# 28Pins_Schem.net
KiCad netlist of a schematic drawn in Altium Designer
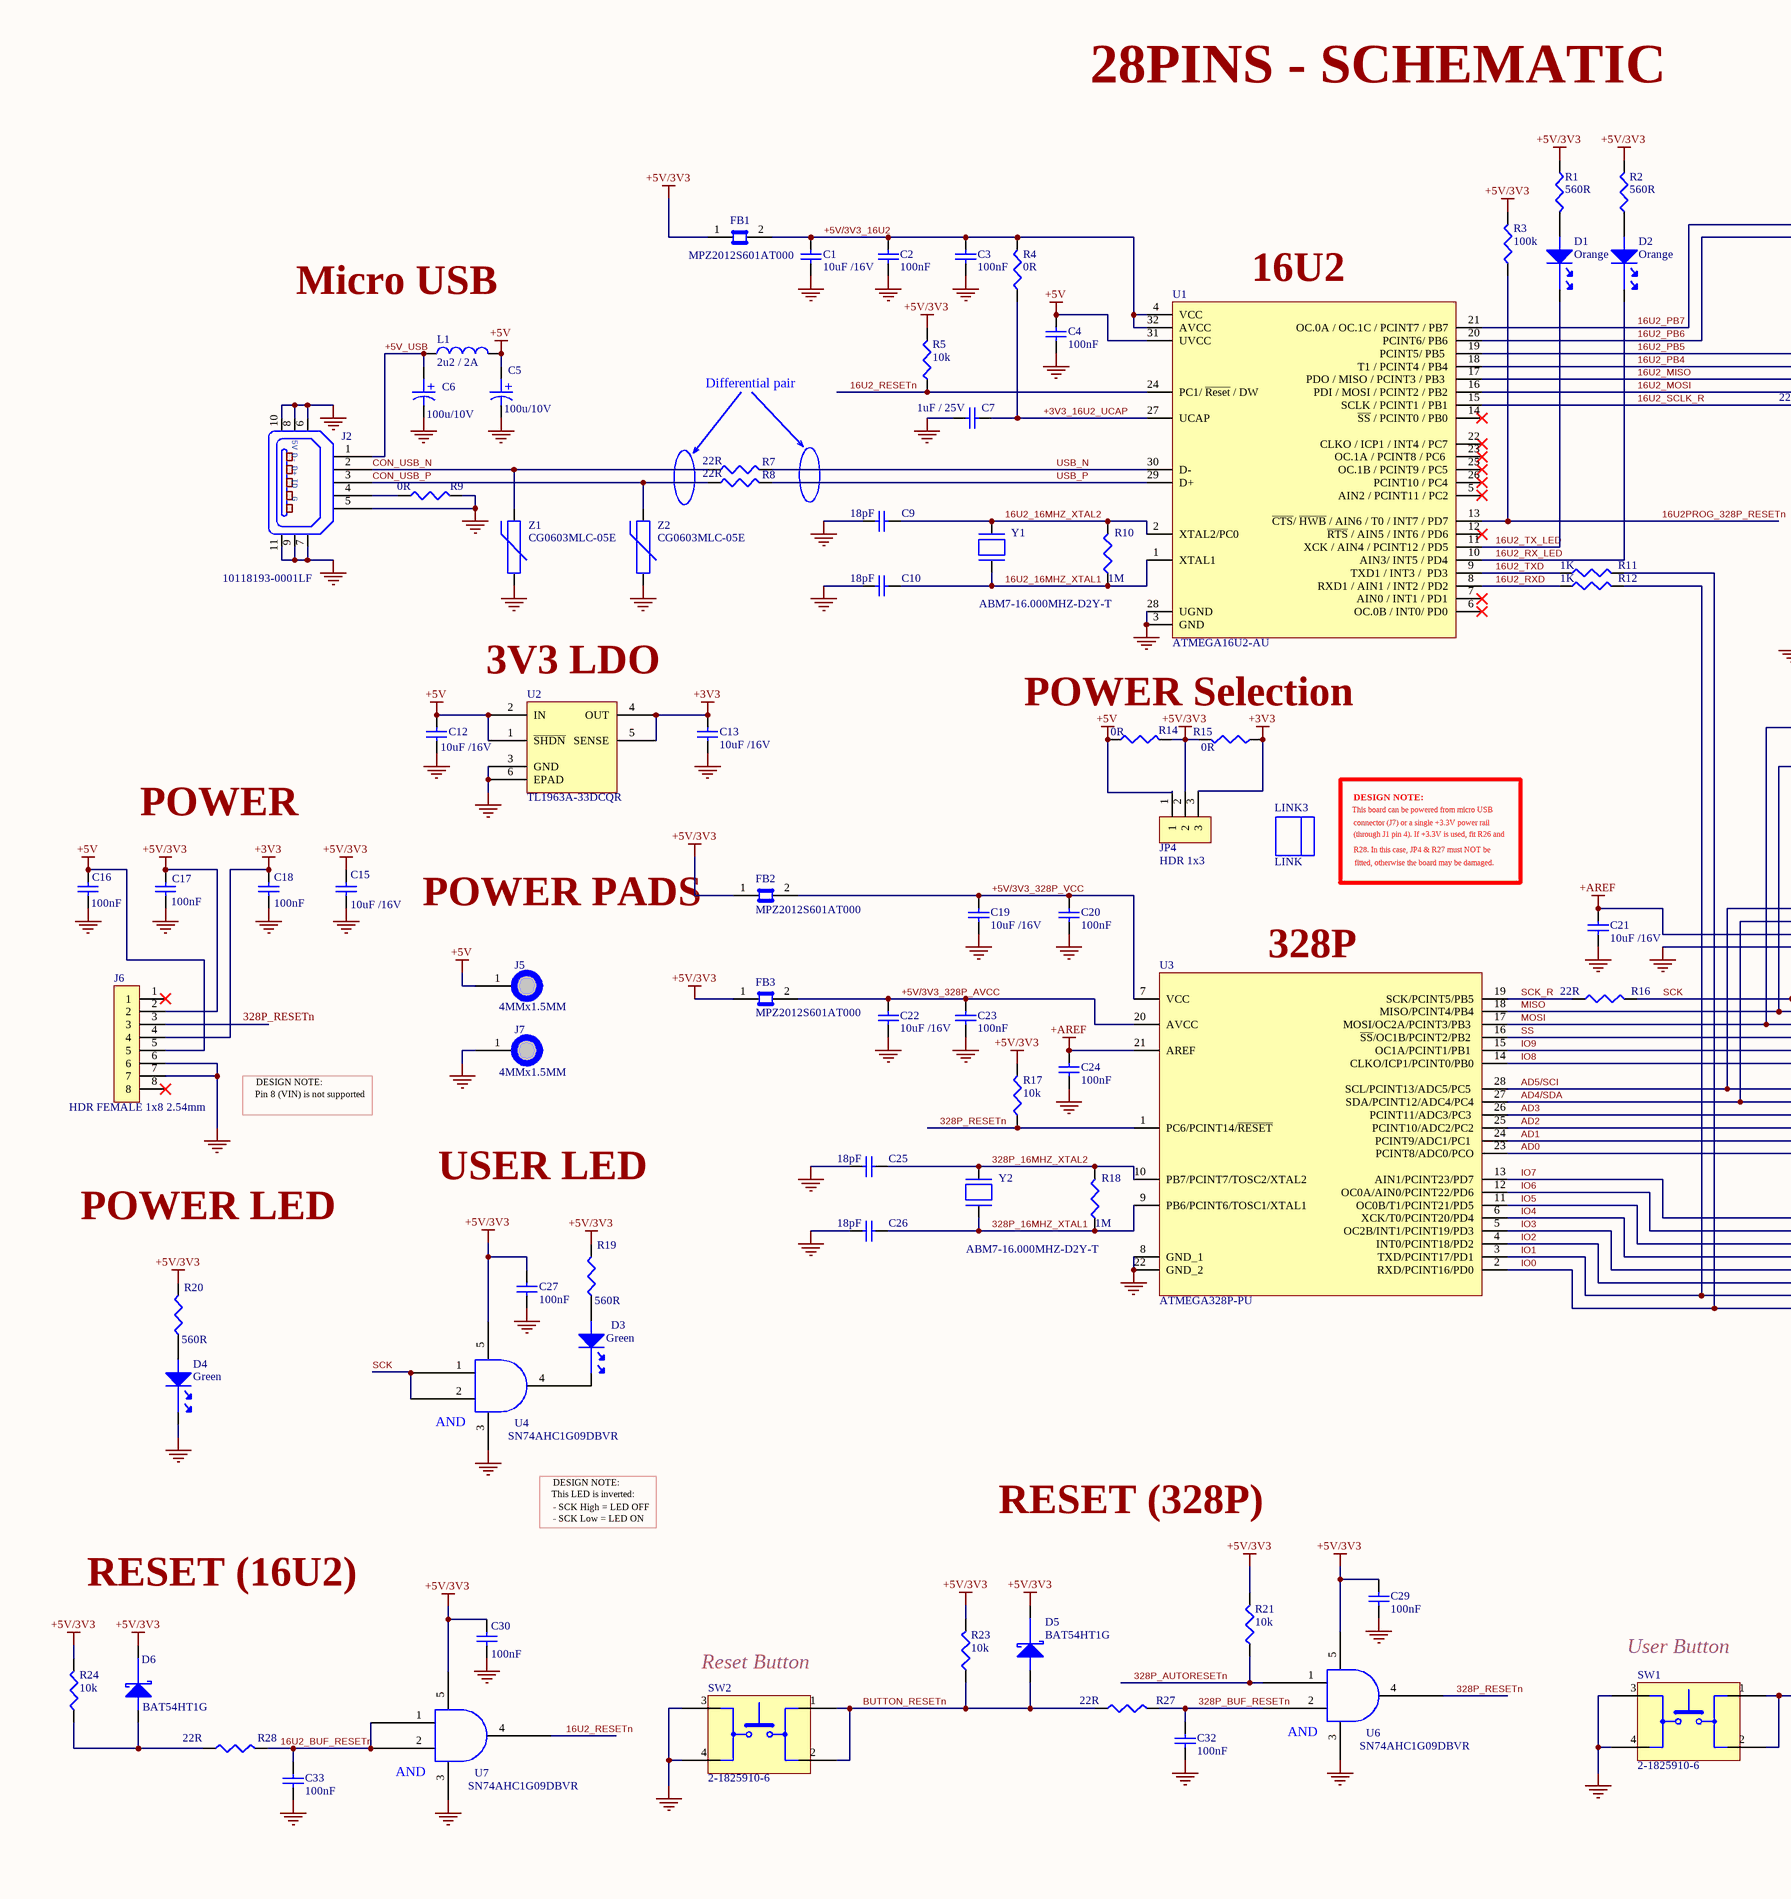
[diagram p0: 28Pins_Schem.SchDoc, left]
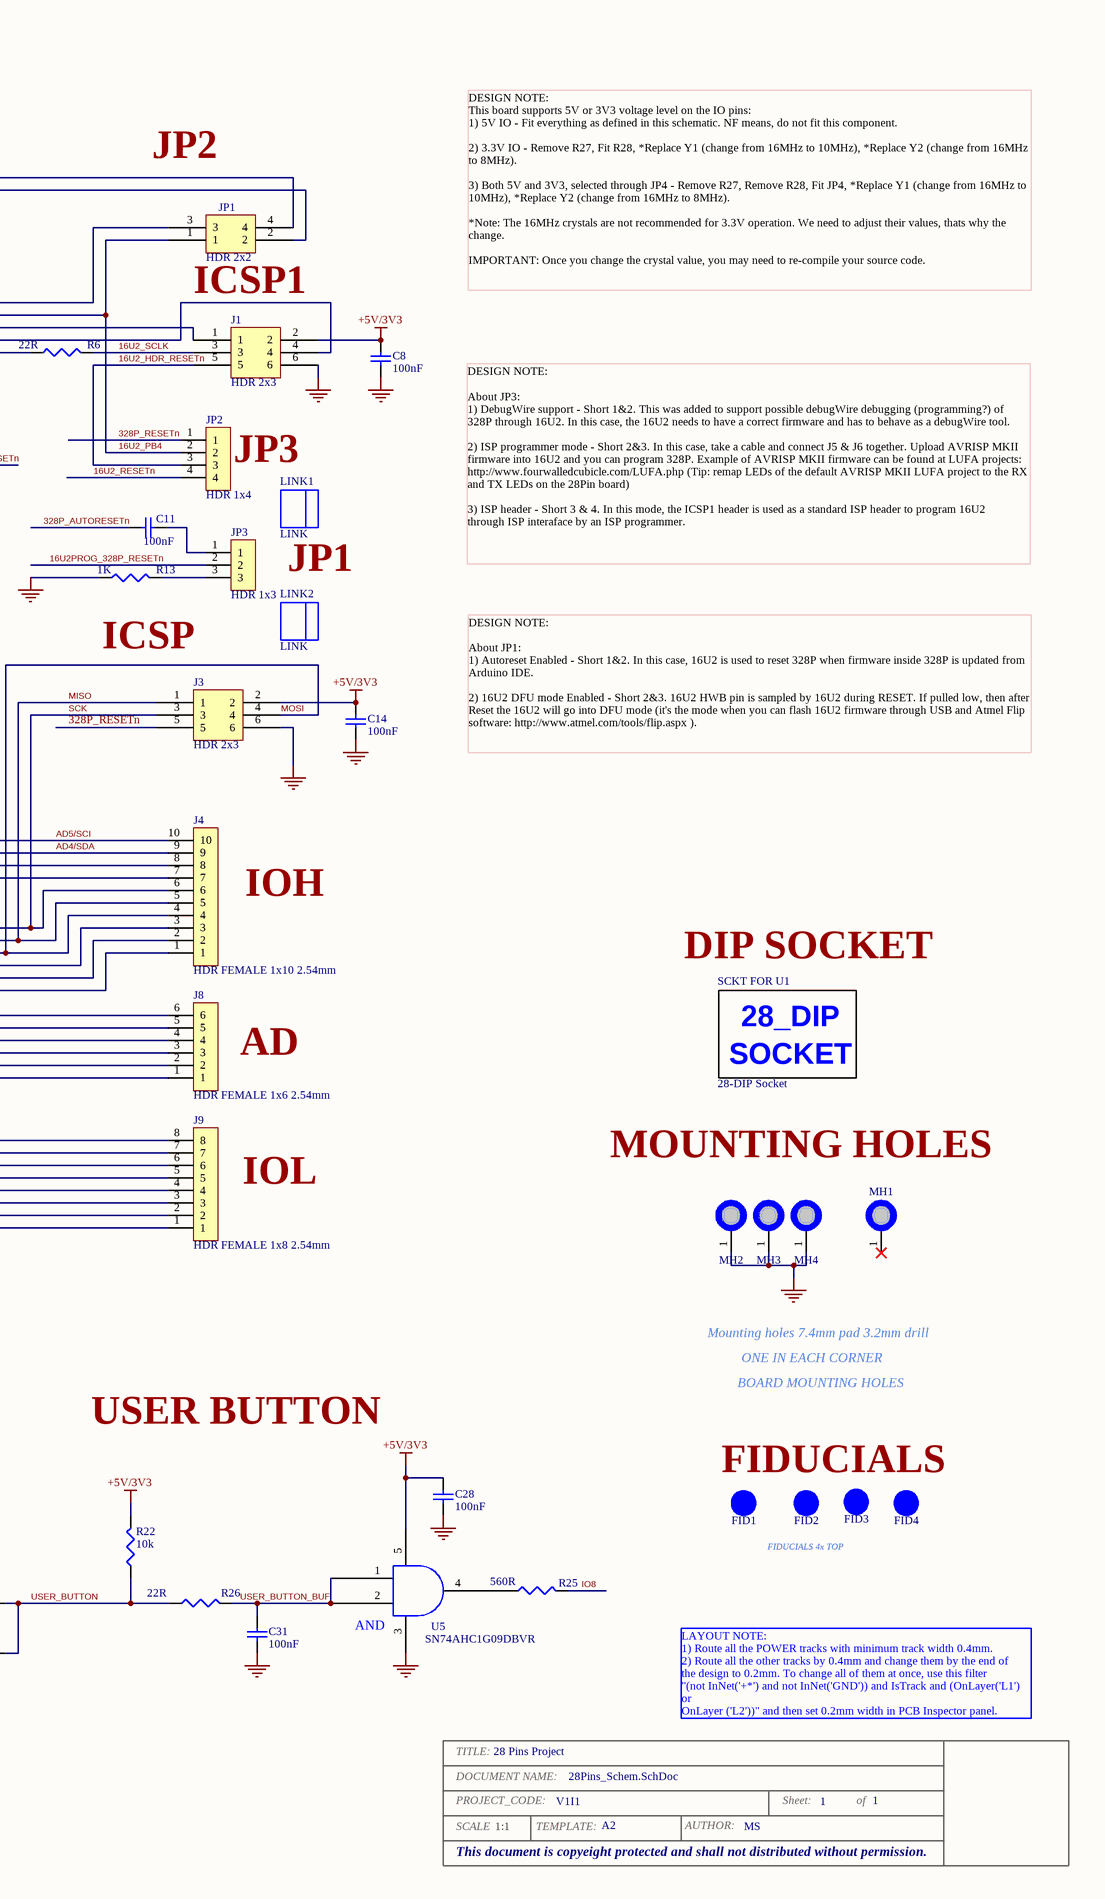
[diagram p1: 28Pins_Schem.SchDoc, right]

(export (version "E")
  (design (tool "Eeschema 10.0.6"))
  (components
    (comp (ref "28 Pins Project")
      (value "TitleBlock")
      (description "Standard Title Block")
      (fields (field (name "TEMPLATE") "A2"))
      (libsource (lib "ms_INTLIB") (part "TitleBlock"))
    )
    (comp (ref "C1")
      (value "10uF /16V")
      (footprint "C0805")
      (fields
        (field (name "MANUFACTURER") "TDK")
        (field (name "MANUFACTURER PART NUMBER") "C2012X5R1C106M125AC")
        (field (name "TOLERANCE") "20%")
      )
      (libsource (lib "28Pins_Project_Schlib") (part "C2012X5R1C106M125AC"))
    )
    (comp (ref "C2")
      (value "100nF")
      (footprint "C0805")
      (description "C Series 0805 0.1 uF 50 V ±10 % Tolerance X7R SMT Multilayer Ceramic Capacitor")
      (fields
        (field (name "MANUFACTURER") "TDK")
        (field (name "MANUFACTURER PART NUMBER") "C2012X7R1H104K085AA")
      )
      (libsource (lib "28Pins_Project_Schlib") (part "C2012X7R1H104K085AA"))
    )
    (comp (ref "C3")
      (value "100nF")
      (footprint "C0805")
      (description "C Series 0805 0.1 uF 50 V ±10 % Tolerance X7R SMT Multilayer Ceramic Capacitor")
      (fields
        (field (name "MANUFACTURER") "TDK")
        (field (name "MANUFACTURER PART NUMBER") "C2012X7R1H104K085AA")
      )
      (libsource (lib "28Pins_Project_Schlib") (part "C2012X7R1H104K085AA"))
    )
    (comp (ref "C4")
      (value "100nF")
      (footprint "C0805")
      (description "C Series 0805 0.1 uF 50 V ±10 % Tolerance X7R SMT Multilayer Ceramic Capacitor")
      (fields
        (field (name "MANUFACTURER") "TDK")
        (field (name "MANUFACTURER PART NUMBER") "C2012X7R1H104K085AA")
      )
      (libsource (lib "28Pins_Project_Schlib") (part "C2012X7R1H104K085AA"))
    )
    (comp (ref "C5")
      (value "100u/10V")
      (footprint "C_ALU_C_SIZE")
      (description "SMD Aluminum Electrolytic Capacitor 100uF ±20% 10V 1000hrs@85°C AEC_D5.0x5.4mm_SM")
      (fields
        (field (name "MANUFACTURER") "Panasonic")
        (field (name "MANUFACTURER PART NUMBER") "EEE-1AA101WR")
      )
      (libsource (lib "28Pins_Project_Schlib") (part "EEE-1AA101WR"))
    )
    (comp (ref "C6")
      (value "100u/10V")
      (footprint "C_ALU_C_SIZE")
      (description "SMD Aluminum Electrolytic Capacitor 100uF ±20% 10V 1000hrs@85°C AEC_D5.0x5.4mm_SM")
      (fields
        (field (name "MANUFACTURER") "Panasonic")
        (field (name "MANUFACTURER PART NUMBER") "EEE-1AA101WR")
      )
      (libsource (lib "28Pins_Project_Schlib") (part "EEE-1AA101WR"))
    )
    (comp (ref "C7")
      (value "1uF / 25V")
      (footprint "C0805")
      (fields
        (field (name "MANUFACTURER") "TDK")
        (field (name "MANUFACTURER PART NUMBER") "C2012X5R1E105K125AA")
        (field (name "TOLERANCE") "10%")
      )
      (libsource (lib "28Pins_Project_Schlib") (part "C2012X5R1E105K125AA"))
    )
    (comp (ref "C8")
      (value "100nF")
      (footprint "C0805")
      (description "C Series 0805 0.1 uF 50 V ±10 % Tolerance X7R SMT Multilayer Ceramic Capacitor")
      (fields
        (field (name "MANUFACTURER") "TDK")
        (field (name "MANUFACTURER PART NUMBER") "C2012X7R1H104K085AA")
      )
      (libsource (lib "28Pins_Project_Schlib") (part "C2012X7R1H104K085AA"))
    )
    (comp (ref "C9")
      (value "18pF")
      (footprint "C0805")
      (description "Cap Ceramic 18pF 50V C0G 5% SMD 0805 125C Paper T/R")
      (fields
        (field (name "MANUFACTURER") "KEMET")
        (field (name "MANUFACTURER PART NUMBER") "C0805C180J5GACTU")
      )
      (libsource (lib "28Pins_Project_Schlib") (part "C0805C180J5GACTU"))
    )
    (comp (ref "C10")
      (value "18pF")
      (footprint "C0805")
      (description "Cap Ceramic 18pF 50V C0G 5% SMD 0805 125C Paper T/R")
      (fields
        (field (name "MANUFACTURER") "KEMET")
        (field (name "MANUFACTURER PART NUMBER") "C0805C180J5GACTU")
      )
      (libsource (lib "28Pins_Project_Schlib") (part "C0805C180J5GACTU"))
    )
    (comp (ref "C11")
      (value "100nF")
      (footprint "C0805")
      (description "C Series 0805 0.1 uF 50 V ±10 % Tolerance X7R SMT Multilayer Ceramic Capacitor")
      (fields
        (field (name "MANUFACTURER") "TDK")
        (field (name "MANUFACTURER PART NUMBER") "C2012X7R1H104K085AA")
      )
      (libsource (lib "28Pins_Project_Schlib") (part "C2012X7R1H104K085AA"))
    )
    (comp (ref "C12")
      (value "10uF /16V")
      (footprint "C0805")
      (fields
        (field (name "MANUFACTURER") "TDK")
        (field (name "MANUFACTURER PART NUMBER") "C2012X5R1C106M125AC")
        (field (name "TOLERANCE") "20%")
      )
      (libsource (lib "28Pins_Project_Schlib") (part "C2012X5R1C106M125AC"))
    )
    (comp (ref "C13")
      (value "10uF /16V")
      (footprint "C0805")
      (fields
        (field (name "MANUFACTURER") "TDK")
        (field (name "MANUFACTURER PART NUMBER") "C2012X5R1C106M125AC")
        (field (name "TOLERANCE") "20%")
      )
      (libsource (lib "28Pins_Project_Schlib") (part "C2012X5R1C106M125AC"))
    )
    (comp (ref "C14")
      (value "100nF")
      (footprint "C0805")
      (description "C Series 0805 0.1 uF 50 V ±10 % Tolerance X7R SMT Multilayer Ceramic Capacitor")
      (fields
        (field (name "MANUFACTURER") "TDK")
        (field (name "MANUFACTURER PART NUMBER") "C2012X7R1H104K085AA")
      )
      (libsource (lib "28Pins_Project_Schlib") (part "C2012X7R1H104K085AA"))
    )
    (comp (ref "C15")
      (value "10uF /16V")
      (footprint "C0805")
      (fields
        (field (name "MANUFACTURER") "TDK")
        (field (name "MANUFACTURER PART NUMBER") "C2012X5R1C106M125AC")
        (field (name "TOLERANCE") "20%")
      )
      (libsource (lib "28Pins_Project_Schlib") (part "C2012X5R1C106M125AC"))
    )
    (comp (ref "C16")
      (value "100nF")
      (footprint "C0805")
      (description "C Series 0805 0.1 uF 50 V ±10 % Tolerance X7R SMT Multilayer Ceramic Capacitor")
      (fields
        (field (name "MANUFACTURER") "TDK")
        (field (name "MANUFACTURER PART NUMBER") "C2012X7R1H104K085AA")
      )
      (libsource (lib "28Pins_Project_Schlib") (part "C2012X7R1H104K085AA"))
    )
    (comp (ref "C17")
      (value "100nF")
      (footprint "C0805")
      (description "C Series 0805 0.1 uF 50 V ±10 % Tolerance X7R SMT Multilayer Ceramic Capacitor")
      (fields
        (field (name "MANUFACTURER") "TDK")
        (field (name "MANUFACTURER PART NUMBER") "C2012X7R1H104K085AA")
      )
      (libsource (lib "28Pins_Project_Schlib") (part "C2012X7R1H104K085AA"))
    )
    (comp (ref "C18")
      (value "100nF")
      (footprint "C0805")
      (description "C Series 0805 0.1 uF 50 V ±10 % Tolerance X7R SMT Multilayer Ceramic Capacitor")
      (fields
        (field (name "MANUFACTURER") "TDK")
        (field (name "MANUFACTURER PART NUMBER") "C2012X7R1H104K085AA")
      )
      (libsource (lib "28Pins_Project_Schlib") (part "C2012X7R1H104K085AA"))
    )
    (comp (ref "C19")
      (value "10uF /16V")
      (footprint "C0805")
      (fields
        (field (name "MANUFACTURER") "TDK")
        (field (name "MANUFACTURER PART NUMBER") "C2012X5R1C106M125AC")
        (field (name "TOLERANCE") "20%")
      )
      (libsource (lib "28Pins_Project_Schlib") (part "C2012X5R1C106M125AC"))
    )
    (comp (ref "C20")
      (value "100nF")
      (footprint "C0805")
      (description "C Series 0805 0.1 uF 50 V ±10 % Tolerance X7R SMT Multilayer Ceramic Capacitor")
      (fields
        (field (name "MANUFACTURER") "TDK")
        (field (name "MANUFACTURER PART NUMBER") "C2012X7R1H104K085AA")
      )
      (libsource (lib "28Pins_Project_Schlib") (part "C2012X7R1H104K085AA"))
    )
    (comp (ref "C21")
      (value "10uF /16V")
      (footprint "C0805")
      (fields
        (field (name "MANUFACTURER") "TDK")
        (field (name "MANUFACTURER PART NUMBER") "C2012X5R1C106M125AC")
        (field (name "TOLERANCE") "20%")
      )
      (libsource (lib "28Pins_Project_Schlib") (part "C2012X5R1C106M125AC"))
    )
    (comp (ref "C22")
      (value "10uF /16V")
      (footprint "C0805")
      (fields
        (field (name "MANUFACTURER") "TDK")
        (field (name "MANUFACTURER PART NUMBER") "C2012X5R1C106M125AC")
        (field (name "TOLERANCE") "20%")
      )
      (libsource (lib "28Pins_Project_Schlib") (part "C2012X5R1C106M125AC"))
    )
    (comp (ref "C23")
      (value "100nF")
      (footprint "C0805")
      (description "C Series 0805 0.1 uF 50 V ±10 % Tolerance X7R SMT Multilayer Ceramic Capacitor")
      (fields
        (field (name "MANUFACTURER") "TDK")
        (field (name "MANUFACTURER PART NUMBER") "C2012X7R1H104K085AA")
      )
      (libsource (lib "28Pins_Project_Schlib") (part "C2012X7R1H104K085AA"))
    )
    (comp (ref "C24")
      (value "100nF")
      (footprint "C0805")
      (description "C Series 0805 0.1 uF 50 V ±10 % Tolerance X7R SMT Multilayer Ceramic Capacitor")
      (fields
        (field (name "MANUFACTURER") "TDK")
        (field (name "MANUFACTURER PART NUMBER") "C2012X7R1H104K085AA")
      )
      (libsource (lib "28Pins_Project_Schlib") (part "C2012X7R1H104K085AA"))
    )
    (comp (ref "C25")
      (value "18pF")
      (footprint "C0805")
      (description "Cap Ceramic 18pF 50V C0G 5% SMD 0805 125C Paper T/R")
      (fields
        (field (name "MANUFACTURER") "KEMET")
        (field (name "MANUFACTURER PART NUMBER") "C0805C180J5GACTU")
      )
      (libsource (lib "28Pins_Project_Schlib") (part "C0805C180J5GACTU"))
    )
    (comp (ref "C26")
      (value "18pF")
      (footprint "C0805")
      (description "Cap Ceramic 18pF 50V C0G 5% SMD 0805 125C Paper T/R")
      (fields
        (field (name "MANUFACTURER") "KEMET")
        (field (name "MANUFACTURER PART NUMBER") "C0805C180J5GACTU")
      )
      (libsource (lib "28Pins_Project_Schlib") (part "C0805C180J5GACTU"))
    )
    (comp (ref "C27")
      (value "100nF")
      (footprint "C0805")
      (description "C Series 0805 0.1 uF 50 V ±10 % Tolerance X7R SMT Multilayer Ceramic Capacitor")
      (fields
        (field (name "MANUFACTURER") "TDK")
        (field (name "MANUFACTURER PART NUMBER") "C2012X7R1H104K085AA")
      )
      (libsource (lib "28Pins_Project_Schlib") (part "C2012X7R1H104K085AA"))
    )
    (comp (ref "C28")
      (value "100nF")
      (footprint "C0805")
      (description "C Series 0805 0.1 uF 50 V ±10 % Tolerance X7R SMT Multilayer Ceramic Capacitor")
      (fields
        (field (name "MANUFACTURER") "TDK")
        (field (name "MANUFACTURER PART NUMBER") "C2012X7R1H104K085AA")
      )
      (libsource (lib "28Pins_Project_Schlib") (part "C2012X7R1H104K085AA"))
    )
    (comp (ref "C29")
      (value "100nF")
      (footprint "C0805")
      (description "C Series 0805 0.1 uF 50 V ±10 % Tolerance X7R SMT Multilayer Ceramic Capacitor")
      (fields
        (field (name "MANUFACTURER") "TDK")
        (field (name "MANUFACTURER PART NUMBER") "C2012X7R1H104K085AA")
      )
      (libsource (lib "28Pins_Project_Schlib") (part "C2012X7R1H104K085AA"))
    )
    (comp (ref "C30")
      (value "100nF")
      (footprint "C0805")
      (description "C Series 0805 0.1 uF 50 V ±10 % Tolerance X7R SMT Multilayer Ceramic Capacitor")
      (fields
        (field (name "MANUFACTURER") "TDK")
        (field (name "MANUFACTURER PART NUMBER") "C2012X7R1H104K085AA")
      )
      (libsource (lib "28Pins_Project_Schlib") (part "C2012X7R1H104K085AA"))
    )
    (comp (ref "C31")
      (value "100nF")
      (footprint "C0805")
      (description "C Series 0805 0.1 uF 50 V ±10 % Tolerance X7R SMT Multilayer Ceramic Capacitor")
      (fields
        (field (name "MANUFACTURER") "TDK")
        (field (name "MANUFACTURER PART NUMBER") "C2012X7R1H104K085AA")
      )
      (libsource (lib "28Pins_Project_Schlib") (part "C2012X7R1H104K085AA"))
    )
    (comp (ref "C32")
      (value "100nF")
      (footprint "C0805")
      (description "C Series 0805 0.1 uF 50 V ±10 % Tolerance X7R SMT Multilayer Ceramic Capacitor")
      (fields
        (field (name "MANUFACTURER") "TDK")
        (field (name "MANUFACTURER PART NUMBER") "C2012X7R1H104K085AA")
      )
      (libsource (lib "28Pins_Project_Schlib") (part "C2012X7R1H104K085AA"))
    )
    (comp (ref "C33")
      (value "100nF")
      (footprint "C0805")
      (description "C Series 0805 0.1 uF 50 V ±10 % Tolerance X7R SMT Multilayer Ceramic Capacitor")
      (fields
        (field (name "MANUFACTURER") "TDK")
        (field (name "MANUFACTURER PART NUMBER") "C2012X7R1H104K085AA")
      )
      (libsource (lib "28Pins_Project_Schlib") (part "C2012X7R1H104K085AA"))
    )
    (comp (ref "D1")
      (value "Orange")
      (footprint "LED_0603")
      (description "Smartled Orange Lc")
      (fields
        (field (name "MANUFACTURER") "Osram Opto")
        (field (name "MANUFACTURER PART NUMBER") "LOL29K-H2K1-24-Z")
      )
      (libsource (lib "28Pins_Project_Schlib") (part "LOL29K-H2K1-24-Z"))
    )
    (comp (ref "D2")
      (value "Orange")
      (footprint "LED_0603")
      (description "Smartled Orange Lc")
      (fields
        (field (name "MANUFACTURER") "Osram Opto")
        (field (name "MANUFACTURER PART NUMBER") "LOL29K-H2K1-24-Z")
      )
      (libsource (lib "28Pins_Project_Schlib") (part "LOL29K-H2K1-24-Z"))
    )
    (comp (ref "D3")
      (value "Green")
      (footprint "LED_0603")
      (description "LED Single Chip Green 570nm 20mA 2-Pin 0603 T/R")
      (fields
        (field (name "MANUFACTURER") "Osram Opto")
        (field (name "MANUFACTURER PART NUMBER") "LGL29K-G2J1-24-Z")
      )
      (libsource (lib "28Pins_Project_Schlib") (part "LGL29K-G2J1-24-Z"))
    )
    (comp (ref "D4")
      (value "Green")
      (footprint "LED_0603")
      (description "LED Single Chip Green 570nm 20mA 2-Pin 0603 T/R")
      (fields
        (field (name "MANUFACTURER") "Osram Opto")
        (field (name "MANUFACTURER PART NUMBER") "LGL29K-G2J1-24-Z")
      )
      (libsource (lib "28Pins_Project_Schlib") (part "LGL29K-G2J1-24-Z"))
    )
    (comp (ref "D5")
      (value "BAT54HT1G")
      (footprint "SOD323")
      (description "VR=30V IF=200mA 10pF P=200mW")
      (fields (field (name "MANUFACTURER") "ON Semiconductor / Fairchild"))
      (libsource (lib "28Pins_Project_Schlib") (part "BAT54HT1G"))
    )
    (comp (ref "D6")
      (value "BAT54HT1G")
      (footprint "SOD323")
      (description "VR=30V IF=200mA 10pF P=200mW")
      (fields (field (name "MANUFACTURER") "ON Semiconductor / Fairchild"))
      (libsource (lib "28Pins_Project_Schlib") (part "BAT54HT1G"))
    )
    (comp (ref "FB1")
      (value "MPZ2012S601AT000")
      (footprint "C0805")
      (description "0805 600Ω ±25% DCR=0.1Ω 2A")
      (fields (field (name "MANUFACTURER") "TDK"))
      (libsource (lib "28Pins_Project_Schlib") (part "MPZ2012S601AT000"))
    )
    (comp (ref "FB2")
      (value "MPZ2012S601AT000")
      (footprint "C0805")
      (description "0805 600Ω ±25% DCR=0.1Ω 2A")
      (fields (field (name "MANUFACTURER") "TDK"))
      (libsource (lib "28Pins_Project_Schlib") (part "MPZ2012S601AT000"))
    )
    (comp (ref "FB3")
      (value "MPZ2012S601AT000")
      (footprint "C0805")
      (description "0805 600Ω ±25% DCR=0.1Ω 2A")
      (fields (field (name "MANUFACTURER") "TDK"))
      (libsource (lib "28Pins_Project_Schlib") (part "MPZ2012S601AT000"))
    )
    (comp (ref "FID1")
      (value "FID_1MMC")
      (footprint "FID_40X120")
      (description "Fiducials 40mm Diameter, 120mm Mask")
      (libsource (lib "28Pins_Project_Schlib") (part "FID_1MMC"))
    )
    (comp (ref "FID2")
      (value "FID_1MMC")
      (footprint "FID_40X120")
      (description "Fiducials 40mm Diameter, 120mm Mask")
      (libsource (lib "28Pins_Project_Schlib") (part "FID_1MMC"))
    )
    (comp (ref "FID3")
      (value "FID_1MMC")
      (footprint "FID_40X120")
      (description "Fiducials 40mm Diameter, 120mm Mask")
      (libsource (lib "28Pins_Project_Schlib") (part "FID_1MMC"))
    )
    (comp (ref "FID4")
      (value "FID_1MMC")
      (footprint "FID_40X120")
      (description "Fiducials 40mm Diameter, 120mm Mask")
      (libsource (lib "28Pins_Project_Schlib") (part "FID_1MMC"))
    )
    (comp (ref "J1")
      (value "HDR 2x3")
      (footprint "HDR_2x3_2.54MM")
      (description "Conn Unshrouded Header HDR 6 POS 2.54mm Solder ST Top Entry Thru-Hole BergStik® Bulk")
      (fields
        (field (name "MANUFACTURER") "Amphenol ICC / FCI")
        (field (name "MANUFACTURER PART NUMBER") "67997-106HLF")
      )
      (libsource (lib "28Pins_Project_Schlib") (part "67997-106HLF"))
    )
    (comp (ref "J2")
      (value "10118193-0001LF")
      (footprint "10118193")
      (description "FCI Right Angle Surface Mount Mount Female USB Connector; 100 V ac; 1.8A")
      (fields (field (name "MANUFACTURER") "Amphenol ICC / FCI"))
      (libsource (lib "28Pins_Project_Schlib") (part "10118193-0001LF"))
    )
    (comp (ref "J3")
      (value "HDR 2x3")
      (footprint "HDR_2x3_2.54MM")
      (description "Conn Unshrouded Header HDR 6 POS 2.54mm Solder ST Top Entry Thru-Hole BergStik® Bulk")
      (fields
        (field (name "MANUFACTURER") "Amphenol ICC / FCI")
        (field (name "MANUFACTURER PART NUMBER") "67997-106HLF")
      )
      (libsource (lib "28Pins_Project_Schlib") (part "67997-106HLF"))
    )
    (comp (ref "J4")
      (value "HDR FEMALE 1x10 2.54mm")
      (footprint "Hdr_female_1x10_2.54mm")
      (description "2.54mm (0.1\") Pitch SIL Vertical PC Tail Socket Assembly, tin, 10 contacts")
      (fields (field (name "MANUFACTURER") "Harwin") (field (name "MANUFACTURER PART NUMBER") "M20-7821046"))
      (libsource (lib "28Pins_Project_Schlib") (part "M20-7821046"))
    )
    (comp (ref "J5")
      (value "4MMx1.5MM")
      (footprint "PAD_WITH_HOLE_4MMx1.5MM")
      (description "Pad with a hole 4mm x 1.5mm")
      (libsource (lib "28Pins_Project_Schlib") (part "PAD_WITH_HOLE_4MMx1.5MM"))
    )
    (comp (ref "J6")
      (value "HDR FEMALE 1x8 2.54mm")
      (footprint "Hdr_female_1x8_2.54mm")
      (description "2.54mm (0.1\") Pitch SIL Vertical PC Tail Socket Assembly, selective gold + tin, 8 contacts")
      (fields (field (name "MANUFACTURER") "Harwin") (field (name "MANUFACTURER PART NUMBER") "M20-7820842"))
      (libsource (lib "28Pins_Project_Schlib") (part "M20-7820842"))
    )
    (comp (ref "J7")
      (value "4MMx1.5MM")
      (footprint "PAD_WITH_HOLE_4MMx1.5MM")
      (description "Pad with a hole 4mm x 1.5mm")
      (libsource (lib "28Pins_Project_Schlib") (part "PAD_WITH_HOLE_4MMx1.5MM"))
    )
    (comp (ref "J8")
      (value "HDR FEMALE 1x6 2.54mm")
      (footprint "Hdr_female_1x6_2.54mm")
      (description "2.54mm (0.1\") Pitch SIL Vertical PC Tail Socket Assembly, tin, 6 contacts")
      (fields (field (name "MANUFACTURER") "Harwin") (field (name "MANUFACTURER PART NUMBER") "M20-7820646"))
      (libsource (lib "28Pins_Project_Schlib") (part "M20-7820646"))
    )
    (comp (ref "J9")
      (value "HDR FEMALE 1x8 2.54mm")
      (footprint "Hdr_female_1x8_2.54mm")
      (description "2.54mm (0.1\") Pitch SIL Vertical PC Tail Socket Assembly, selective gold + tin, 8 contacts")
      (fields (field (name "MANUFACTURER") "Harwin") (field (name "MANUFACTURER PART NUMBER") "M20-7820842"))
      (libsource (lib "") (part "M20-7820842_1"))
    )
    (comp (ref "JP1")
      (value "HDR 2x2")
      (footprint "HDR_2x2_2.54MM")
      (description "Conn Unshrouded Header HDR 4 POS 2.54mm Solder ST Top Entry Thru-Hole BergStik® Bulk")
      (fields
        (field (name "MANUFACTURER") "Amphenol ICC / FCI")
        (field (name "MANUFACTURER PART NUMBER") "68602-204HLF")
      )
      (libsource (lib "28Pins_Project_Schlib") (part "68602-204HLF"))
    )
    (comp (ref "JP2")
      (value "HDR 1x4")
      (footprint "Hdr_1x4_2.54mm")
      (description "Conn Unshrouded Header HDR 4 POS 2.54mm Solder ST Thru-Hole Bag")
      (fields
        (field (name "MANUFACTURER") "Amphenol ICC / FCI")
        (field (name "MANUFACTURER PART NUMBER") "68001-204HLF")
      )
      (libsource (lib "28Pins_Project_Schlib") (part "68001-204HLF"))
    )
    (comp (ref "JP3")
      (value "HDR 1x3")
      (footprint "Hdr_1x3_2.54mm")
      (description "Conn Unshrouded Header HDR 3 POS 2.54mm Solder ST Top Entry Thru-Hole BergStik® Automotive Bulk")
      (fields
        (field (name "MANUFACTURER") "Amphenol ICC / FCI")
        (field (name "MANUFACTURER PART NUMBER") "68000-103HLF")
      )
      (libsource (lib "28Pins_Project_Schlib") (part "68000-103HLF"))
    )
    (comp (ref "JP4")
      (value "HDR 1x3")
      (footprint "Hdr_1x3_2.54mm")
      (description "Conn Unshrouded Header HDR 3 POS 2.54mm Solder ST Top Entry Thru-Hole BergStik® Automotive Bulk")
      (fields
        (field (name "MANUFACTURER") "Amphenol ICC / FCI")
        (field (name "MANUFACTURER PART NUMBER") "68000-103HLF")
      )
      (libsource (lib "") (part "68000-103HLF_1"))
    )
    (comp (ref "L1")
      (value "2u2 / 2A")
      (footprint "C1210_IND")
      (description "Inductor RF Chip Wirewound 2.2uH 20% 100KHz 1.13A 0.104Ohm DCR 1210 T/R")
      (fields
        (field (name "MANUFACTURER") "KEMET")
        (field (name "MANUFACTURER PART NUMBER") "L1210R2R2MDWIT")
      )
      (libsource (lib "28Pins_Project_Schlib") (part "L1210R2R2MDWIT"))
    )
    (comp (ref "LINK1")
      (value "LINK")
      (description "2 Position 2.54 mm Centerline Single Circuit Open Top Jumper")
      (fields
        (field (name "MANUFACTURER") "Sullins")
        (field (name "MANUFACTURER PART NUMBER") "QPC02SXGN-RC")
      )
      (libsource (lib "28Pins_Project_Schlib") (part "QPC02SXGN-RC"))
    )
    (comp (ref "LINK2")
      (value "LINK")
      (description "2 Position 2.54 mm Centerline Single Circuit Open Top Jumper")
      (fields
        (field (name "MANUFACTURER") "Sullins")
        (field (name "MANUFACTURER PART NUMBER") "QPC02SXGN-RC")
      )
      (libsource (lib "28Pins_Project_Schlib") (part "QPC02SXGN-RC"))
    )
    (comp (ref "LINK3")
      (value "LINK")
      (description "2 Position 2.54 mm Centerline Single Circuit Open Top Jumper")
      (fields
        (field (name "MANUFACTURER") "Sullins")
        (field (name "MANUFACTURER PART NUMBER") "QPC02SXGN-RC")
      )
      (libsource (lib "28Pins_Project_Schlib") (part "QPC02SXGN-RC"))
    )
    (comp (ref "MH1")
      (value "MH_7.4MMNC_3.2MMD")
      (footprint "MH_7.4MMD_3.2MMD_NON_COPPER_NPTH")
      (description "Mounting Hole 7.4mm Diameter (Non Copper), 3.2mm Drill NPTH")
      (libsource (lib "28Pins_Project_Schlib") (part "MH_7.4MMNC_3.2MMD"))
    )
    (comp (ref "MH2")
      (value "MH_7.4MMC_3.2MMD")
      (footprint "MH_7.4MMD_3.2MMD")
      (description "Mounting Hole 7.4mm Diameter, 3.2mm Drill")
      (libsource (lib "28Pins_Project_Schlib") (part "MH_7.4MMC_3.2MMD"))
    )
    (comp (ref "MH3")
      (value "MH_7.4MMC_3.2MMD")
      (footprint "MH_7.4MMD_3.2MMD")
      (description "Mounting Hole 7.4mm Diameter, 3.2mm Drill")
      (libsource (lib "28Pins_Project_Schlib") (part "MH_7.4MMC_3.2MMD"))
    )
    (comp (ref "MH4")
      (value "MH_7.4MMC_3.2MMD")
      (footprint "MH_7.4MMD_3.2MMD")
      (description "Mounting Hole 7.4mm Diameter, 3.2mm Drill")
      (libsource (lib "28Pins_Project_Schlib") (part "MH_7.4MMC_3.2MMD"))
    )
    (comp (ref "R1")
      (value "560R")
      (footprint "R0805")
      (description "Chip resistance 560Ω ± 1.00% 0.125W ± 100ppm/℃ 0805")
      (fields
        (field (name "MANUFACTURER") "Yageo")
        (field (name "MANUFACTURER PART NUMBER") "RC0805FR-07560RL")
      )
      (libsource (lib "28Pins_Project_Schlib") (part "RC0805FR-07560RL"))
    )
    (comp (ref "R2")
      (value "560R")
      (footprint "R0805")
      (description "Chip resistance 560Ω ± 1.00% 0.125W ± 100ppm/℃ 0805")
      (fields
        (field (name "MANUFACTURER") "Yageo")
        (field (name "MANUFACTURER PART NUMBER") "RC0805FR-07560RL")
      )
      (libsource (lib "28Pins_Project_Schlib") (part "RC0805FR-07560RL"))
    )
    (comp (ref "R3")
      (value "100k")
      (footprint "R0805")
      (description "Chip resistance 100000Ω ± 1.00% 0.125W ± 100ppm/℃ 0805")
      (fields
        (field (name "MANUFACTURER") "Yageo")
        (field (name "MANUFACTURER PART NUMBER") "RC0805FR-07100KL")
      )
      (libsource (lib "28Pins_Project_Schlib") (part "RC0805FR-07100KL"))
    )
    (comp (ref "R4")
      (value "0R")
      (footprint "R0805")
      (description "Chip resistance 0Ω ±5% 1/8W 0805")
      (fields
        (field (name "MANUFACTURER") "Yageo")
        (field (name "MANUFACTURER PART NUMBER") "RC0805JR-070RL")
      )
      (libsource (lib "28Pins_Project_Schlib") (part "RC0805JR-070RL"))
    )
    (comp (ref "R5")
      (value "10k")
      (footprint "R0805")
      (description "Chip resistance 10000Ω ± 1.00% 0.125W ± 100ppm/℃ 0805")
      (fields
        (field (name "MANUFACTURER") "Yageo")
        (field (name "MANUFACTURER PART NUMBER") "RC0805FR-0710KL")
      )
      (libsource (lib "28Pins_Project_Schlib") (part "RC0805FR-0710KL"))
    )
    (comp (ref "R6")
      (value "22R")
      (footprint "R0805")
      (description "Chip resistance 22Ω ± 1.00% 0.125W ± 100ppm/℃ 0805")
      (fields
        (field (name "MANUFACTURER") "Yageo")
        (field (name "MANUFACTURER PART NUMBER") "RC0805FR-0722RL")
      )
      (libsource (lib "28Pins_Project_Schlib") (part "RC0805FR-0722RL"))
    )
    (comp (ref "R7")
      (value "22R")
      (footprint "R0805")
      (description "Chip resistance 22Ω ± 1.00% 0.125W ± 100ppm/℃ 0805")
      (fields
        (field (name "MANUFACTURER") "Yageo")
        (field (name "MANUFACTURER PART NUMBER") "RC0805FR-0722RL")
      )
      (libsource (lib "28Pins_Project_Schlib") (part "RC0805FR-0722RL"))
    )
    (comp (ref "R8")
      (value "22R")
      (footprint "R0805")
      (description "Chip resistance 22Ω ± 1.00% 0.125W ± 100ppm/℃ 0805")
      (fields
        (field (name "MANUFACTURER") "Yageo")
        (field (name "MANUFACTURER PART NUMBER") "RC0805FR-0722RL")
      )
      (libsource (lib "28Pins_Project_Schlib") (part "RC0805FR-0722RL"))
    )
    (comp (ref "R9")
      (value "0R")
      (footprint "R0805")
      (description "Chip resistance 0Ω ±5% 1/8W 0805")
      (fields
        (field (name "MANUFACTURER") "Yageo")
        (field (name "MANUFACTURER PART NUMBER") "RC0805JR-070RL")
      )
      (libsource (lib "28Pins_Project_Schlib") (part "RC0805JR-070RL"))
    )
    (comp (ref "R10")
      (value "1M")
      (footprint "R0805")
      (description "Chip resistance 1000000Ω ± 1.00% 0.125W ± 100ppm/℃ 0805")
      (fields
        (field (name "MANUFACTURER") "Yageo")
        (field (name "MANUFACTURER PART NUMBER") "RC0805FR-071ML")
      )
      (libsource (lib "28Pins_Project_Schlib") (part "RC0805FR-071ML"))
    )
    (comp (ref "R11")
      (value "1K")
      (footprint "R0805")
      (description "Chip resistance 1000Ω ± 1.00% 0.125W ± 100ppm/℃ 0805")
      (fields
        (field (name "MANUFACTURER") "Yageo")
        (field (name "MANUFACTURER PART NUMBER") "RC0805FR-071KL")
      )
      (libsource (lib "28Pins_Project_Schlib") (part "RC0805FR-071KL"))
    )
    (comp (ref "R12")
      (value "1K")
      (footprint "R0805")
      (description "Chip resistance 1000Ω ± 1.00% 0.125W ± 100ppm/℃ 0805")
      (fields
        (field (name "MANUFACTURER") "Yageo")
        (field (name "MANUFACTURER PART NUMBER") "RC0805FR-071KL")
      )
      (libsource (lib "28Pins_Project_Schlib") (part "RC0805FR-071KL"))
    )
    (comp (ref "R13")
      (value "1K")
      (footprint "R0805")
      (description "Chip resistance 1000Ω ± 1.00% 0.125W ± 100ppm/℃ 0805")
      (fields
        (field (name "MANUFACTURER") "Yageo")
        (field (name "MANUFACTURER PART NUMBER") "RC0805FR-071KL")
      )
      (libsource (lib "28Pins_Project_Schlib") (part "RC0805FR-071KL"))
    )
    (comp (ref "R14")
      (value "0R")
      (footprint "R0805")
      (description "Chip resistance 0Ω ±5% 1/8W 0805")
      (fields
        (field (name "MANUFACTURER") "Yageo")
        (field (name "MANUFACTURER PART NUMBER") "RC0805JR-070RL")
      )
      (libsource (lib "28Pins_Project_Schlib") (part "RC0805JR-070RL"))
    )
    (comp (ref "R15")
      (value "0R")
      (footprint "R0805")
      (description "Chip resistance 0Ω ±5% 1/8W 0805")
      (fields
        (field (name "MANUFACTURER") "Yageo")
        (field (name "MANUFACTURER PART NUMBER") "RC0805JR-070RL")
      )
      (libsource (lib "28Pins_Project_Schlib") (part "RC0805JR-070RL"))
    )
    (comp (ref "R16")
      (value "22R")
      (footprint "R0805")
      (description "Chip resistance 22Ω ± 1.00% 0.125W ± 100ppm/℃ 0805")
      (fields
        (field (name "MANUFACTURER") "Yageo")
        (field (name "MANUFACTURER PART NUMBER") "RC0805FR-0722RL")
      )
      (libsource (lib "28Pins_Project_Schlib") (part "RC0805FR-0722RL"))
    )
    (comp (ref "R17")
      (value "10k")
      (footprint "R0805")
      (description "Chip resistance 10000Ω ± 1.00% 0.125W ± 100ppm/℃ 0805")
      (fields
        (field (name "MANUFACTURER") "Yageo")
        (field (name "MANUFACTURER PART NUMBER") "RC0805FR-0710KL")
      )
      (libsource (lib "28Pins_Project_Schlib") (part "RC0805FR-0710KL"))
    )
    (comp (ref "R18")
      (value "1M")
      (footprint "R0805")
      (description "Chip resistance 1000000Ω ± 1.00% 0.125W ± 100ppm/℃ 0805")
      (fields
        (field (name "MANUFACTURER") "Yageo")
        (field (name "MANUFACTURER PART NUMBER") "RC0805FR-071ML")
      )
      (libsource (lib "28Pins_Project_Schlib") (part "RC0805FR-071ML"))
    )
    (comp (ref "R19")
      (value "560R")
      (footprint "R0805")
      (description "Chip resistance 560Ω ± 1.00% 0.125W ± 100ppm/℃ 0805")
      (fields
        (field (name "MANUFACTURER") "Yageo")
        (field (name "MANUFACTURER PART NUMBER") "RC0805FR-07560RL")
      )
      (libsource (lib "28Pins_Project_Schlib") (part "RC0805FR-07560RL"))
    )
    (comp (ref "R20")
      (value "560R")
      (footprint "R0805")
      (description "Chip resistance 560Ω ± 1.00% 0.125W ± 100ppm/℃ 0805")
      (fields
        (field (name "MANUFACTURER") "Yageo")
        (field (name "MANUFACTURER PART NUMBER") "RC0805FR-07560RL")
      )
      (libsource (lib "28Pins_Project_Schlib") (part "RC0805FR-07560RL"))
    )
    (comp (ref "R21")
      (value "10k")
      (footprint "R0805")
      (description "Chip resistance 10000Ω ± 1.00% 0.125W ± 100ppm/℃ 0805")
      (fields
        (field (name "MANUFACTURER") "Yageo")
        (field (name "MANUFACTURER PART NUMBER") "RC0805FR-0710KL")
      )
      (libsource (lib "28Pins_Project_Schlib") (part "RC0805FR-0710KL"))
    )
    (comp (ref "R22")
      (value "10k")
      (footprint "R0805")
      (description "Chip resistance 10000Ω ± 1.00% 0.125W ± 100ppm/℃ 0805")
      (fields
        (field (name "MANUFACTURER") "Yageo")
        (field (name "MANUFACTURER PART NUMBER") "RC0805FR-0710KL")
      )
      (libsource (lib "28Pins_Project_Schlib") (part "RC0805FR-0710KL"))
    )
    (comp (ref "R23")
      (value "10k")
      (footprint "R0805")
      (description "Chip resistance 10000Ω ± 1.00% 0.125W ± 100ppm/℃ 0805")
      (fields
        (field (name "MANUFACTURER") "Yageo")
        (field (name "MANUFACTURER PART NUMBER") "RC0805FR-0710KL")
      )
      (libsource (lib "28Pins_Project_Schlib") (part "RC0805FR-0710KL"))
    )
    (comp (ref "R24")
      (value "10k")
      (footprint "R0805")
      (description "Chip resistance 10000Ω ± 1.00% 0.125W ± 100ppm/℃ 0805")
      (fields
        (field (name "MANUFACTURER") "Yageo")
        (field (name "MANUFACTURER PART NUMBER") "RC0805FR-0710KL")
      )
      (libsource (lib "28Pins_Project_Schlib") (part "RC0805FR-0710KL"))
    )
    (comp (ref "R25")
      (value "560R")
      (footprint "R0805")
      (description "Chip resistance 560Ω ± 1.00% 0.125W ± 100ppm/℃ 0805")
      (fields
        (field (name "MANUFACTURER") "Yageo")
        (field (name "MANUFACTURER PART NUMBER") "RC0805FR-07560RL")
      )
      (libsource (lib "28Pins_Project_Schlib") (part "RC0805FR-07560RL"))
    )
    (comp (ref "R26")
      (value "22R")
      (footprint "R0805")
      (description "Chip resistance 22Ω ± 1.00% 0.125W ± 100ppm/℃ 0805")
      (fields
        (field (name "MANUFACTURER") "Yageo")
        (field (name "MANUFACTURER PART NUMBER") "RC0805FR-0722RL")
      )
      (libsource (lib "28Pins_Project_Schlib") (part "RC0805FR-0722RL"))
    )
    (comp (ref "R27")
      (value "22R")
      (footprint "R0805")
      (description "Chip resistance 22Ω ± 1.00% 0.125W ± 100ppm/℃ 0805")
      (fields
        (field (name "MANUFACTURER") "Yageo")
        (field (name "MANUFACTURER PART NUMBER") "RC0805FR-0722RL")
      )
      (libsource (lib "28Pins_Project_Schlib") (part "RC0805FR-0722RL"))
    )
    (comp (ref "R28")
      (value "22R")
      (footprint "R0805")
      (description "Chip resistance 22Ω ± 1.00% 0.125W ± 100ppm/℃ 0805")
      (fields
        (field (name "MANUFACTURER") "Yageo")
        (field (name "MANUFACTURER PART NUMBER") "RC0805FR-0722RL")
      )
      (libsource (lib "28Pins_Project_Schlib") (part "RC0805FR-0722RL"))
    )
    (comp (ref "SCKT FOR U1")
      (value "28-DIP Socket")
      (footprint "28_DIP_7.62mm_SOCKET")
      (description "Socket DIP 28Cnts DualWipe 0.3InSpc. PhosphorBronze Nickel KinkedTail 4800Series")
      (fields (field (name "MANUFACTURER") "3M") (field (name "MANUFACTURER PART NUMBER") "4828-3004-CP"))
      (libsource (lib "28Pins_Project_Schlib") (part "4828-3004-CP"))
    )
    (comp (ref "SW1")
      (value "2-1825910-6")
      (footprint "2-1825910-6")
      (fields (field (name "MANUFACTURER") "TE Connectivity AMP"))
      (libsource (lib "28Pins_Project_Schlib") (part "2-1825910-6"))
    )
    (comp (ref "SW2")
      (value "2-1825910-6")
      (footprint "2-1825910-6")
      (fields (field (name "MANUFACTURER") "TE Connectivity AMP"))
      (libsource (lib "28Pins_Project_Schlib") (part "2-1825910-6"))
    )
    (comp (ref "U1")
      (value "ATMEGA16U2-AU")
      (footprint "TQFP32")
      (description "8-bit AVR MCU, 16 KB, 512 Bytes, 16 MHz, 2.7 to 5.5V, TQFP-32, RoHS")
      (fields (field (name "MANUFACTURER") "Microchip"))
      (libsource (lib "28Pins_Project_Schlib") (part "ATMEGA16U2-AU"))
    )
    (comp (ref "U2")
      (value "TL1963A-33DCQR")
      (footprint "DCQ (R-PDSO-G6)")
      (description "LDO Regulator Pos 3.3V 1.5A 6-Pin(5+Tab) SOT-223 T/R")
      (fields (field (name "MANUFACTURER") "Texas Instruments"))
      (libsource (lib "28Pins_Project_Schlib") (part "TL1963A-33DCQR"))
    )
    (comp (ref "U3")
      (value "ATMEGA328P-PU")
      (footprint "28_DIP_7.62MM")
      (description "IC MCU 8BIT 32KB FLASH 28DIP")
      (fields (field (name "MANUFACTURER") "Microchip"))
      (libsource (lib "28Pins_Project_Schlib") (part "ATMEGA328P-PU"))
    )
    (comp (ref "U4")
      (value "SN74AHC1G09DBVR")
      (footprint "DBV_SOT_23_5")
      (description "Single 2-input, 2-V to 5.5-V AND gate with open-drain outputs 5-SOT-23 -55 to 125")
      (fields (field (name "MANUFACTURER") "Texas Instruments"))
      (libsource (lib "28Pins_Project_Schlib") (part "SN74AHC1G09DBVR"))
    )
    (comp (ref "U5")
      (value "SN74AHC1G09DBVR")
      (footprint "DBV_SOT_23_5")
      (description "Single 2-input, 2-V to 5.5-V AND gate with open-drain outputs 5-SOT-23 -55 to 125")
      (fields (field (name "MANUFACTURER") "Texas Instruments"))
      (libsource (lib "28Pins_Project_Schlib") (part "SN74AHC1G09DBVR"))
    )
    (comp (ref "U6")
      (value "SN74AHC1G09DBVR")
      (footprint "DBV_SOT_23_5")
      (description "Single 2-input, 2-V to 5.5-V AND gate with open-drain outputs 5-SOT-23 -55 to 125")
      (fields (field (name "MANUFACTURER") "Texas Instruments"))
      (libsource (lib "28Pins_Project_Schlib") (part "SN74AHC1G09DBVR"))
    )
    (comp (ref "U7")
      (value "SN74AHC1G09DBVR")
      (footprint "DBV_SOT_23_5")
      (description "Single 2-input, 2-V to 5.5-V AND gate with open-drain outputs 5-SOT-23 -55 to 125")
      (fields (field (name "MANUFACTURER") "Texas Instruments"))
      (libsource (lib "28Pins_Project_Schlib") (part "SN74AHC1G09DBVR"))
    )
    (comp (ref "Y1")
      (value "ABM7-16.000MHZ-D2Y-T")
      (footprint "AMB7_V1_1_BIG")
      (description "16MHz ±20ppm Crystal 18pF 50 Ohm -40°C ~ 85°C Surface Mount 2-SMD, No Leads (DFN, LCC)")
      (fields (field (name "MANUFACTURER") "Abracon") (field (name "TOLERANCE") "20ppm"))
      (libsource (lib "28Pins_Project_Schlib") (part "ABM7-16.000MHZ-D2Y-T"))
    )
    (comp (ref "Y2")
      (value "ABM7-16.000MHZ-D2Y-T")
      (footprint "AMB7_V1_1_BIG")
      (description "16MHz ±20ppm Crystal 18pF 50 Ohm -40°C ~ 85°C Surface Mount 2-SMD, No Leads (DFN, LCC)")
      (fields (field (name "MANUFACTURER") "Abracon") (field (name "TOLERANCE") "20ppm"))
      (libsource (lib "28Pins_Project_Schlib") (part "ABM7-16.000MHZ-D2Y-T"))
    )
    (comp (ref "Z1")
      (value "CG0603MLC-05E")
      (footprint "R0603")
      (description "ESD Suppressor Multilayer Varistor 5V Automotive 2-Pin Case 0603(1608Metric) T/R")
      (fields (field (name "MANUFACTURER") "Bourns") (field (name "VOLTAGE") "5V"))
      (libsource (lib "28Pins_Project_Schlib") (part "CG0603MLC-05E"))
    )
    (comp (ref "Z2")
      (value "CG0603MLC-05E")
      (footprint "R0603")
      (description "ESD Suppressor Multilayer Varistor 5V Automotive 2-Pin Case 0603(1608Metric) T/R")
      (fields (field (name "MANUFACTURER") "Bourns") (field (name "VOLTAGE") "5V"))
      (libsource (lib "28Pins_Project_Schlib") (part "CG0603MLC-05E"))
    )
  )
  (nets
    (net (code "1") (name "+3V3") (class "Default")
      (node (ref "C13") (pin "1") (pinfunction "1_1") (pintype "passive"))
      (node (ref "C18") (pin "1") (pinfunction "1_1") (pintype "passive"))
      (node (ref "J6") (pin "4") (pinfunction "4_4") (pintype "passive"))
      (node (ref "JP4") (pin "3") (pinfunction "3_3") (pintype "passive"))
      (node (ref "R15") (pin "1") (pinfunction "1_1") (pintype "passive"))
      (node (ref "U2") (pin "4") (pinfunction "OUT_4") (pintype "passive"))
      (node (ref "U2") (pin "5") (pinfunction "SENSE_5") (pintype "passive"))
    )
    (net (code "2") (name "+5V") (class "Default")
      (node (ref "C12") (pin "1") (pinfunction "1_1") (pintype "passive"))
      (node (ref "C16") (pin "1") (pinfunction "1_1") (pintype "passive"))
      (node (ref "C4") (pin "1") (pinfunction "1_1") (pintype "passive"))
      (node (ref "C5") (pin "1") (pinfunction "1_1") (pintype "passive"))
      (node (ref "J5") (pin "1") (pinfunction "1_1") (pintype "passive"))
      (node (ref "J6") (pin "5") (pinfunction "5_5") (pintype "passive"))
      (node (ref "JP4") (pin "1") (pinfunction "1_1") (pintype "passive"))
      (node (ref "L1") (pin "2") (pinfunction "2_2") (pintype "passive"))
      (node (ref "R14") (pin "1") (pinfunction "1_1") (pintype "passive"))
      (node (ref "U1") (pin "31") (pinfunction "UVCC_31") (pintype "passive"))
      (node (ref "U2") (pin "1") (pinfunction "~{SHDN}_1") (pintype "passive"))
      (node (ref "U2") (pin "2") (pinfunction "IN_2") (pintype "passive"))
    )
    (net (code "3") (name "+5V{slash}3V3") (class "Default")
      (node (ref "C14") (pin "1") (pinfunction "1_1") (pintype "passive"))
      (node (ref "C15") (pin "1") (pinfunction "1_1") (pintype "passive"))
      (node (ref "C17") (pin "1") (pinfunction "1_1") (pintype "passive"))
      (node (ref "C27") (pin "1") (pinfunction "1_1") (pintype "passive"))
      (node (ref "C28") (pin "1") (pinfunction "1_1") (pintype "passive"))
      (node (ref "C29") (pin "1") (pinfunction "1_1") (pintype "passive"))
      (node (ref "C30") (pin "1") (pinfunction "1_1") (pintype "passive"))
      (node (ref "C8") (pin "1") (pinfunction "1_1") (pintype "passive"))
      (node (ref "D5") (pin "1") (pinfunction "Cathode_1") (pintype "passive"))
      (node (ref "D6") (pin "1") (pinfunction "Cathode_1") (pintype "passive"))
      (node (ref "FB1") (pin "1") (pinfunction "1_1") (pintype "passive"))
      (node (ref "FB2") (pin "1") (pinfunction "1_1") (pintype "passive"))
      (node (ref "FB3") (pin "1") (pinfunction "1_1") (pintype "passive"))
      (node (ref "J1") (pin "2") (pinfunction "2_2") (pintype "passive"))
      (node (ref "J3") (pin "2") (pinfunction "2_2") (pintype "passive"))
      (node (ref "J6") (pin "2") (pinfunction "2_2") (pintype "passive"))
      (node (ref "JP4") (pin "2") (pinfunction "2_2") (pintype "passive"))
      (node (ref "R1") (pin "1") (pinfunction "1_1") (pintype "passive"))
      (node (ref "R14") (pin "2") (pinfunction "2_2") (pintype "passive"))
      (node (ref "R15") (pin "2") (pinfunction "2_2") (pintype "passive"))
      (node (ref "R17") (pin "2") (pinfunction "2_2") (pintype "passive"))
      (node (ref "R19") (pin "2") (pinfunction "2_2") (pintype "passive"))
      (node (ref "R2") (pin "2") (pinfunction "2_2") (pintype "passive"))
      (node (ref "R20") (pin "2") (pinfunction "2_2") (pintype "passive"))
      (node (ref "R21") (pin "2") (pinfunction "2_2") (pintype "passive"))
      (node (ref "R22") (pin "2") (pinfunction "2_2") (pintype "passive"))
      (node (ref "R23") (pin "2") (pinfunction "2_2") (pintype "passive"))
      (node (ref "R24") (pin "2") (pinfunction "2_2") (pintype "passive"))
      (node (ref "R3") (pin "2") (pinfunction "2_2") (pintype "passive"))
      (node (ref "R5") (pin "2") (pinfunction "2_2") (pintype "passive"))
      (node (ref "U4") (pin "5") (pinfunction "5_5") (pintype "passive"))
      (node (ref "U5") (pin "5") (pinfunction "5_5") (pintype "passive"))
      (node (ref "U6") (pin "5") (pinfunction "5_5") (pintype "passive"))
      (node (ref "U7") (pin "5") (pinfunction "5_5") (pintype "passive"))
    )
    (net (code "4") (name "+AREF") (class "Default")
      (node (ref "C21") (pin "1") (pinfunction "1_1") (pintype "passive"))
      (node (ref "C24") (pin "1") (pinfunction "1_1") (pintype "passive"))
      (node (ref "J4") (pin "8") (pinfunction "8_8") (pintype "passive"))
      (node (ref "U3") (pin "21") (pinfunction "AREF_21") (pintype "passive"))
    )
    (net (code "5") (name "/+3V3_16U2_UCAP") (class "Default")
      (node (ref "C7") (pin "2") (pinfunction "2_2") (pintype "passive"))
      (node (ref "R4") (pin "1") (pinfunction "1_1") (pintype "passive"))
      (node (ref "U1") (pin "27") (pinfunction "UCAP_27") (pintype "passive"))
    )
    (net (code "6") (name "/+5V_USB") (class "Default")
      (node (ref "C6") (pin "1") (pinfunction "1_1") (pintype "passive"))
      (node (ref "J2") (pin "1") (pinfunction "1_1") (pintype "passive"))
      (node (ref "L1") (pin "1") (pinfunction "1_1") (pintype "passive"))
    )
    (net (code "7") (name "/+5V{slash}3V3_16U2") (class "Default")
      (node (ref "C1") (pin "1") (pinfunction "1_1") (pintype "passive"))
      (node (ref "C2") (pin "1") (pinfunction "1_1") (pintype "passive"))
      (node (ref "C3") (pin "1") (pinfunction "1_1") (pintype "passive"))
      (node (ref "FB1") (pin "2") (pinfunction "2_2") (pintype "passive"))
      (node (ref "R4") (pin "2") (pinfunction "2_2") (pintype "passive"))
      (node (ref "U1") (pin "32") (pinfunction "AVCC_32") (pintype "passive"))
      (node (ref "U1") (pin "4") (pinfunction "VCC_4") (pintype "passive"))
    )
    (net (code "8") (name "/+5V{slash}3V3_328P_AVCC") (class "Default")
      (node (ref "C22") (pin "1") (pinfunction "1_1") (pintype "passive"))
      (node (ref "C23") (pin "1") (pinfunction "1_1") (pintype "passive"))
      (node (ref "FB3") (pin "2") (pinfunction "2_2") (pintype "passive"))
      (node (ref "U3") (pin "20") (pinfunction "AVCC_20") (pintype "passive"))
    )
    (net (code "9") (name "/+5V{slash}3V3_328P_VCC") (class "Default")
      (node (ref "C19") (pin "1") (pinfunction "1_1") (pintype "passive"))
      (node (ref "C20") (pin "1") (pinfunction "1_1") (pintype "passive"))
      (node (ref "FB2") (pin "2") (pinfunction "2_2") (pintype "passive"))
      (node (ref "U3") (pin "7") (pinfunction "VCC_7") (pintype "passive"))
    )
    (net (code "10") (name "/16U2PROG_328P_RESETn") (class "Default")
      (node (ref "JP3") (pin "2") (pinfunction "2_2") (pintype "passive"))
      (node (ref "R3") (pin "1") (pinfunction "1_1") (pintype "passive"))
      (node (ref "U1") (pin "13") (pinfunction "~{CTS}/_~{HWB}_/_AIN6_/_T0_/_INT7_/_PD7_13") (pintype "passive"))
    )
    (net (code "11") (name "/16U2_16MHZ_XTAL1") (class "Default")
      (node (ref "C10") (pin "2") (pinfunction "2_2") (pintype "passive"))
      (node (ref "R10") (pin "1") (pinfunction "1_1") (pintype "passive"))
      (node (ref "U1") (pin "1") (pinfunction "XTAL1_1") (pintype "passive"))
      (node (ref "Y1") (pin "1") (pinfunction "1_1") (pintype "passive"))
    )
    (net (code "12") (name "/16U2_16MHZ_XTAL2") (class "Default")
      (node (ref "C9") (pin "2") (pinfunction "2_2") (pintype "passive"))
      (node (ref "R10") (pin "2") (pinfunction "2_2") (pintype "passive"))
      (node (ref "U1") (pin "2") (pinfunction "XTAL2/PC0_2") (pintype "passive"))
      (node (ref "Y1") (pin "2") (pinfunction "2_2") (pintype "passive"))
    )
    (net (code "13") (name "/16U2_BUF_RESETn") (class "Default")
      (node (ref "C33") (pin "1") (pinfunction "1_1") (pintype "passive"))
      (node (ref "R28") (pin "2") (pinfunction "2_2") (pintype "passive"))
      (node (ref "U7") (pin "1") (pinfunction "1_1") (pintype "passive"))
      (node (ref "U7") (pin "2") (pinfunction "2_2") (pintype "passive"))
    )
    (net (code "14") (name "/16U2_HDR_RESETn") (class "Default")
      (node (ref "J1") (pin "5") (pinfunction "5_5") (pintype "passive"))
      (node (ref "JP2") (pin "3") (pinfunction "3_3") (pintype "passive"))
    )
    (net (code "15") (name "/16U2_MISO") (class "Default")
      (node (ref "J1") (pin "1") (pinfunction "1_1") (pintype "passive"))
      (node (ref "U1") (pin "17") (pinfunction "PDO_/_MISO_/_PCINT3_/_PB3_17") (pintype "passive"))
    )
    (net (code "16") (name "/16U2_MOSI") (class "Default")
      (node (ref "J1") (pin "4") (pinfunction "4_4") (pintype "passive"))
      (node (ref "U1") (pin "16") (pinfunction "PDI_/_MOSI_/_PCINT2_/_PB2_16") (pintype "passive"))
    )
    (net (code "17") (name "/16U2_PB4") (class "Default")
      (node (ref "JP1") (pin "1") (pinfunction "1_1") (pintype "passive"))
      (node (ref "JP2") (pin "2") (pinfunction "2_2") (pintype "passive"))
      (node (ref "U1") (pin "18") (pinfunction "T1_/_PCINT4_/_PB4_18") (pintype "passive"))
    )
    (net (code "18") (name "/16U2_PB5") (class "Default")
      (node (ref "JP1") (pin "3") (pinfunction "3_3") (pintype "passive"))
      (node (ref "U1") (pin "19") (pinfunction "PCINT5/_PB5_19") (pintype "passive"))
    )
    (net (code "19") (name "/16U2_PB6") (class "Default")
      (node (ref "JP1") (pin "2") (pinfunction "2_2") (pintype "passive"))
      (node (ref "U1") (pin "20") (pinfunction "PCINT6/_PB6_20") (pintype "passive"))
    )
    (net (code "20") (name "/16U2_PB7") (class "Default")
      (node (ref "JP1") (pin "4") (pinfunction "4_4") (pintype "passive"))
      (node (ref "U1") (pin "21") (pinfunction "OC.0A_/_OC.1C_/_PCINT7_/_PB7_21") (pintype "passive"))
    )
    (net (code "21") (name "/16U2_RESETn") (class "Default")
      (node (ref "JP2") (pin "4") (pinfunction "4_4") (pintype "passive"))
      (node (ref "R5") (pin "1") (pinfunction "1_1") (pintype "passive"))
      (node (ref "U1") (pin "24") (pinfunction "PC1/_~{Reset}_/_DW_24") (pintype "passive"))
      (node (ref "U7") (pin "4") (pinfunction "4_4") (pintype "passive"))
    )
    (net (code "22") (name "/16U2_RXD") (class "Default")
      (node (ref "R12") (pin "1") (pinfunction "1_1") (pintype "passive"))
      (node (ref "U1") (pin "8") (pinfunction "RXD1_/_AIN1_/_INT2_/_PD2_8") (pintype "passive"))
    )
    (net (code "23") (name "/16U2_RX_LED") (class "Default")
      (node (ref "D2") (pin "1") (pinfunction "Cathode_1") (pintype "passive"))
      (node (ref "U1") (pin "10") (pinfunction "AIN3/_INT5_/_PD4_10") (pintype "passive"))
    )
    (net (code "24") (name "/16U2_SCLK") (class "Default")
      (node (ref "J1") (pin "3") (pinfunction "3_3") (pintype "passive"))
      (node (ref "R6") (pin "2") (pinfunction "2_2") (pintype "passive"))
    )
    (net (code "25") (name "/16U2_SCLK_R") (class "Default")
      (node (ref "R6") (pin "1") (pinfunction "1_1") (pintype "passive"))
      (node (ref "U1") (pin "15") (pinfunction "SCLK_/_PCINT1_/_PB1_15") (pintype "passive"))
    )
    (net (code "26") (name "/16U2_TXD") (class "Default")
      (node (ref "R11") (pin "1") (pinfunction "1_1") (pintype "passive"))
      (node (ref "U1") (pin "9") (pinfunction "TXD1_/_INT3_/__PD3_9") (pintype "passive"))
    )
    (net (code "27") (name "/16U2_TX_LED") (class "Default")
      (node (ref "D1") (pin "1") (pinfunction "Cathode_1") (pintype "passive"))
      (node (ref "U1") (pin "11") (pinfunction "XCK_/_AIN4_/_PCINT12_/_PD5_11") (pintype "passive"))
    )
    (net (code "28") (name "/328P_16MHZ_XTAL1") (class "Default")
      (node (ref "C26") (pin "2") (pinfunction "2_2") (pintype "passive"))
      (node (ref "R18") (pin "1") (pinfunction "1_1") (pintype "passive"))
      (node (ref "U3") (pin "9") (pinfunction "PB6/PCINT6/TOSC1/XTAL1_9") (pintype "passive"))
      (node (ref "Y2") (pin "1") (pinfunction "1_1") (pintype "passive"))
    )
    (net (code "29") (name "/328P_16MHZ_XTAL2") (class "Default")
      (node (ref "C25") (pin "2") (pinfunction "2_2") (pintype "passive"))
      (node (ref "R18") (pin "2") (pinfunction "2_2") (pintype "passive"))
      (node (ref "U3") (pin "10") (pinfunction "PB7/PCINT7/TOSC2/XTAL2_10") (pintype "passive"))
      (node (ref "Y2") (pin "2") (pinfunction "2_2") (pintype "passive"))
    )
    (net (code "30") (name "/328P_AUTORESETn") (class "Default")
      (node (ref "C11") (pin "2") (pinfunction "2_2") (pintype "passive"))
      (node (ref "R21") (pin "1") (pinfunction "1_1") (pintype "passive"))
      (node (ref "U6") (pin "1") (pinfunction "1_1") (pintype "passive"))
    )
    (net (code "31") (name "/328P_BUF_RESETn") (class "Default")
      (node (ref "C32") (pin "1") (pinfunction "1_1") (pintype "passive"))
      (node (ref "R27") (pin "2") (pinfunction "2_2") (pintype "passive"))
      (node (ref "U6") (pin "2") (pinfunction "2_2") (pintype "passive"))
    )
    (net (code "32") (name "/328P_RESETn") (class "Default")
      (node (ref "J3") (pin "5") (pinfunction "5_5") (pintype "passive"))
      (node (ref "J6") (pin "3") (pinfunction "3_3") (pintype "passive"))
      (node (ref "JP2") (pin "1") (pinfunction "1_1") (pintype "passive"))
      (node (ref "R17") (pin "1") (pinfunction "1_1") (pintype "passive"))
      (node (ref "U3") (pin "1") (pinfunction "PC6/PCINT14/~{RESET}_1") (pintype "passive"))
      (node (ref "U6") (pin "4") (pinfunction "4_4") (pintype "passive"))
    )
    (net (code "33") (name "/AD0") (class "Default")
      (node (ref "J8") (pin "1") (pinfunction "1_1") (pintype "passive"))
      (node (ref "U3") (pin "23") (pinfunction "PCINT8/ADC0/PCO_23") (pintype "passive"))
    )
    (net (code "34") (name "/AD1") (class "Default")
      (node (ref "J8") (pin "2") (pinfunction "2_2") (pintype "passive"))
      (node (ref "U3") (pin "24") (pinfunction "PCINT9/ADC1/PC1_24") (pintype "passive"))
    )
    (net (code "35") (name "/AD2") (class "Default")
      (node (ref "J8") (pin "3") (pinfunction "3_3") (pintype "passive"))
      (node (ref "U3") (pin "25") (pinfunction "_PCINT10/ADC2/PC2_25") (pintype "passive"))
    )
    (net (code "36") (name "/AD3") (class "Default")
      (node (ref "J8") (pin "4") (pinfunction "4_4") (pintype "passive"))
      (node (ref "U3") (pin "26") (pinfunction "PCINT11/ADC3/PC3_26") (pintype "passive"))
    )
    (net (code "37") (name "/AD4{slash}SDA") (class "Default")
      (node (ref "J4") (pin "9") (pinfunction "9_9") (pintype "passive"))
      (node (ref "J8") (pin "5") (pinfunction "5_5") (pintype "passive"))
      (node (ref "U3") (pin "27") (pinfunction "SDA/PCINT12/ADC4/PC4_27") (pintype "passive"))
    )
    (net (code "38") (name "/AD5{slash}SCI") (class "Default")
      (node (ref "J4") (pin "10") (pinfunction "10_10") (pintype "passive"))
      (node (ref "J8") (pin "6") (pinfunction "6_6") (pintype "passive"))
      (node (ref "U3") (pin "28") (pinfunction "SCL/PCINT13/ADC5/PC5_28") (pintype "passive"))
    )
    (net (code "39") (name "/BUTTON_RESETn") (class "Default")
      (node (ref "D5") (pin "2") (pinfunction "Anode_2") (pintype "passive"))
      (node (ref "R23") (pin "1") (pinfunction "1_1") (pintype "passive"))
      (node (ref "R27") (pin "1") (pinfunction "1_1") (pintype "passive"))
      (node (ref "SW2") (pin "1") (pinfunction "1_1") (pintype "passive"))
      (node (ref "SW2") (pin "2") (pinfunction "2_2") (pintype "passive"))
    )
    (net (code "40") (name "/CON_USB_N") (class "Default")
      (node (ref "J2") (pin "2") (pinfunction "2_2") (pintype "passive"))
      (node (ref "R7") (pin "1") (pinfunction "1_1") (pintype "passive"))
      (node (ref "Z1") (pin "2") (pinfunction "2_2") (pintype "passive"))
    )
    (net (code "41") (name "/CON_USB_P") (class "Default")
      (node (ref "J2") (pin "3") (pinfunction "3_3") (pintype "passive"))
      (node (ref "R8") (pin "1") (pinfunction "1_1") (pintype "passive"))
      (node (ref "Z2") (pin "2") (pinfunction "2_2") (pintype "passive"))
    )
    (net (code "42") (name "/IO0") (class "Default")
      (node (ref "J9") (pin "1") (pinfunction "1_1") (pintype "passive"))
      (node (ref "R11") (pin "2") (pinfunction "2_2") (pintype "passive"))
      (node (ref "U3") (pin "2") (pinfunction "RXD/PCINT16/PD0_2") (pintype "passive"))
    )
    (net (code "43") (name "/IO1") (class "Default")
      (node (ref "J9") (pin "2") (pinfunction "2_2") (pintype "passive"))
      (node (ref "R12") (pin "2") (pinfunction "2_2") (pintype "passive"))
      (node (ref "U3") (pin "3") (pinfunction "TXD/PCINT17/PD1_3") (pintype "passive"))
    )
    (net (code "44") (name "/IO2") (class "Default")
      (node (ref "J9") (pin "3") (pinfunction "3_3") (pintype "passive"))
      (node (ref "U3") (pin "4") (pinfunction "INT0/PCINT18/PD2_4") (pintype "passive"))
    )
    (net (code "45") (name "/IO3") (class "Default")
      (node (ref "J9") (pin "4") (pinfunction "4_4") (pintype "passive"))
      (node (ref "U3") (pin "5") (pinfunction "OC2B/INT1/PCINT19/PD3_5") (pintype "passive"))
    )
    (net (code "46") (name "/IO4") (class "Default")
      (node (ref "J9") (pin "5") (pinfunction "5_5") (pintype "passive"))
      (node (ref "U3") (pin "6") (pinfunction "XCK/T0/PCINT20/PD4_6") (pintype "passive"))
    )
    (net (code "47") (name "/IO5") (class "Default")
      (node (ref "J9") (pin "6") (pinfunction "6_6") (pintype "passive"))
      (node (ref "U3") (pin "11") (pinfunction "OC0B/T1/PCINT21/PD5_11") (pintype "passive"))
    )
    (net (code "48") (name "/IO6") (class "Default")
      (node (ref "J9") (pin "7") (pinfunction "7_7") (pintype "passive"))
      (node (ref "U3") (pin "12") (pinfunction "OC0A/AIN0/PCINT22/PD6_12") (pintype "passive"))
    )
    (net (code "49") (name "/IO7") (class "Default")
      (node (ref "J9") (pin "8") (pinfunction "8_8") (pintype "passive"))
      (node (ref "U3") (pin "13") (pinfunction "AIN1/PCINT23/PD7_13") (pintype "passive"))
    )
    (net (code "50") (name "/IO8") (class "Default")
      (node (ref "J4") (pin "1") (pinfunction "1_1") (pintype "passive"))
      (node (ref "R25") (pin "2") (pinfunction "2_2") (pintype "passive"))
      (node (ref "U3") (pin "14") (pinfunction "CLKO/ICP1/PCINT0/PB0_14") (pintype "passive"))
    )
    (net (code "51") (name "/IO9") (class "Default")
      (node (ref "J4") (pin "2") (pinfunction "2_2") (pintype "passive"))
      (node (ref "U3") (pin "15") (pinfunction "OC1A/PCINT1/PB1_15") (pintype "passive"))
    )
    (net (code "52") (name "/MISO") (class "Default")
      (node (ref "J3") (pin "1") (pinfunction "1_1") (pintype "passive"))
      (node (ref "J4") (pin "5") (pinfunction "5_5") (pintype "passive"))
      (node (ref "U3") (pin "18") (pinfunction "MISO/PCINT4/PB4_18") (pintype "passive"))
    )
    (net (code "53") (name "/MOSI") (class "Default")
      (node (ref "J3") (pin "4") (pinfunction "4_4") (pintype "passive"))
      (node (ref "J4") (pin "4") (pinfunction "4_4") (pintype "passive"))
      (node (ref "U3") (pin "17") (pinfunction "MOSI/OC2A/PCINT3/PB3_17") (pintype "passive"))
    )
    (net (code "54") (name "/SCK") (class "Default")
      (node (ref "J3") (pin "3") (pinfunction "3_3") (pintype "passive"))
      (node (ref "J4") (pin "6") (pinfunction "6_6") (pintype "passive"))
      (node (ref "R16") (pin "2") (pinfunction "2_2") (pintype "passive"))
      (node (ref "U4") (pin "1") (pinfunction "1_1") (pintype "passive"))
      (node (ref "U4") (pin "2") (pinfunction "2_2") (pintype "passive"))
    )
    (net (code "55") (name "/SCK_R") (class "Default")
      (node (ref "R16") (pin "1") (pinfunction "1_1") (pintype "passive"))
      (node (ref "U3") (pin "19") (pinfunction "SCK/PCINT5/PB5_19") (pintype "passive"))
    )
    (net (code "56") (name "/SS") (class "Default")
      (node (ref "J4") (pin "3") (pinfunction "3_3") (pintype "passive"))
      (node (ref "U3") (pin "16") (pinfunction "~{SS}/OC1B/PCINT2/PB2_16") (pintype "passive"))
    )
    (net (code "57") (name "/USB_N") (class "Default")
      (node (ref "R7") (pin "2") (pinfunction "2_2") (pintype "passive"))
      (node (ref "U1") (pin "30") (pinfunction "D-_30") (pintype "passive"))
    )
    (net (code "58") (name "/USB_P") (class "Default")
      (node (ref "R8") (pin "2") (pinfunction "2_2") (pintype "passive"))
      (node (ref "U1") (pin "29") (pinfunction "D+_29") (pintype "passive"))
    )
    (net (code "59") (name "/USER_BUTTON") (class "Default")
      (node (ref "R22") (pin "1") (pinfunction "1_1") (pintype "passive"))
      (node (ref "R26") (pin "1") (pinfunction "1_1") (pintype "passive"))
      (node (ref "SW1") (pin "1") (pinfunction "1_1") (pintype "passive"))
      (node (ref "SW1") (pin "2") (pinfunction "2_2") (pintype "passive"))
    )
    (net (code "60") (name "/USER_BUTTON_BUF") (class "Default")
      (node (ref "C31") (pin "1") (pinfunction "1_1") (pintype "passive"))
      (node (ref "R26") (pin "2") (pinfunction "2_2") (pintype "passive"))
      (node (ref "U5") (pin "1") (pinfunction "1_1") (pintype "passive"))
      (node (ref "U5") (pin "2") (pinfunction "2_2") (pintype "passive"))
    )
    (net (code "61") (name "GND") (class "Default")
      (node (ref "C1") (pin "2") (pinfunction "2_2") (pintype "passive"))
      (node (ref "C10") (pin "1") (pinfunction "1_1") (pintype "passive"))
      (node (ref "C12") (pin "2") (pinfunction "2_2") (pintype "passive"))
      (node (ref "C13") (pin "2") (pinfunction "2_2") (pintype "passive"))
      (node (ref "C14") (pin "2") (pinfunction "2_2") (pintype "passive"))
      (node (ref "C15") (pin "2") (pinfunction "2_2") (pintype "passive"))
      (node (ref "C16") (pin "2") (pinfunction "2_2") (pintype "passive"))
      (node (ref "C17") (pin "2") (pinfunction "2_2") (pintype "passive"))
      (node (ref "C18") (pin "2") (pinfunction "2_2") (pintype "passive"))
      (node (ref "C19") (pin "2") (pinfunction "2_2") (pintype "passive"))
      (node (ref "C2") (pin "2") (pinfunction "2_2") (pintype "passive"))
      (node (ref "C20") (pin "2") (pinfunction "2_2") (pintype "passive"))
      (node (ref "C21") (pin "2") (pinfunction "2_2") (pintype "passive"))
      (node (ref "C22") (pin "2") (pinfunction "2_2") (pintype "passive"))
      (node (ref "C23") (pin "2") (pinfunction "2_2") (pintype "passive"))
      (node (ref "C24") (pin "2") (pinfunction "2_2") (pintype "passive"))
      (node (ref "C25") (pin "1") (pinfunction "1_1") (pintype "passive"))
      (node (ref "C26") (pin "1") (pinfunction "1_1") (pintype "passive"))
      (node (ref "C27") (pin "2") (pinfunction "2_2") (pintype "passive"))
      (node (ref "C28") (pin "2") (pinfunction "2_2") (pintype "passive"))
      (node (ref "C29") (pin "2") (pinfunction "2_2") (pintype "passive"))
      (node (ref "C3") (pin "2") (pinfunction "2_2") (pintype "passive"))
      (node (ref "C30") (pin "2") (pinfunction "2_2") (pintype "passive"))
      (node (ref "C31") (pin "2") (pinfunction "2_2") (pintype "passive"))
      (node (ref "C32") (pin "2") (pinfunction "2_2") (pintype "passive"))
      (node (ref "C33") (pin "2") (pinfunction "2_2") (pintype "passive"))
      (node (ref "C4") (pin "2") (pinfunction "2_2") (pintype "passive"))
      (node (ref "C5") (pin "2") (pinfunction "2_2") (pintype "passive"))
      (node (ref "C6") (pin "2") (pinfunction "2_2") (pintype "passive"))
      (node (ref "C7") (pin "1") (pinfunction "1_1") (pintype "passive"))
      (node (ref "C8") (pin "2") (pinfunction "2_2") (pintype "passive"))
      (node (ref "C9") (pin "1") (pinfunction "1_1") (pintype "passive"))
      (node (ref "D4") (pin "1") (pinfunction "Cathode_1") (pintype "passive"))
      (node (ref "J1") (pin "6") (pinfunction "6_6") (pintype "passive"))
      (node (ref "J2") (pin "10") (pinfunction "10_10") (pintype "passive"))
      (node (ref "J2") (pin "11") (pinfunction "11_11") (pintype "passive"))
      (node (ref "J2") (pin "5") (pinfunction "5_5") (pintype "passive"))
      (node (ref "J2") (pin "6") (pinfunction "6_6") (pintype "passive"))
      (node (ref "J2") (pin "7") (pinfunction "7_7") (pintype "passive"))
      (node (ref "J2") (pin "8") (pinfunction "8_8") (pintype "passive"))
      (node (ref "J2") (pin "9") (pinfunction "9_9") (pintype "passive"))
      (node (ref "J3") (pin "6") (pinfunction "6_6") (pintype "passive"))
      (node (ref "J4") (pin "7") (pinfunction "7_7") (pintype "passive"))
      (node (ref "J6") (pin "6") (pinfunction "6_6") (pintype "passive"))
      (node (ref "J6") (pin "7") (pinfunction "7_7") (pintype "passive"))
      (node (ref "J7") (pin "1") (pinfunction "1_1") (pintype "passive"))
      (node (ref "MH2") (pin "1") (pinfunction "1_1") (pintype "passive"))
      (node (ref "MH3") (pin "1") (pinfunction "1_1") (pintype "passive"))
      (node (ref "MH4") (pin "1") (pinfunction "1_1") (pintype "passive"))
      (node (ref "R13") (pin "1") (pinfunction "1_1") (pintype "passive"))
      (node (ref "R9") (pin "2") (pinfunction "2_2") (pintype "passive"))
      (node (ref "SW1") (pin "3") (pinfunction "3_3") (pintype "passive"))
      (node (ref "SW1") (pin "4") (pinfunction "4_4") (pintype "passive"))
      (node (ref "SW2") (pin "3") (pinfunction "3_3") (pintype "passive"))
      (node (ref "SW2") (pin "4") (pinfunction "4_4") (pintype "passive"))
      (node (ref "U1") (pin "28") (pinfunction "UGND_28") (pintype "passive"))
      (node (ref "U1") (pin "3") (pinfunction "GND_3") (pintype "passive"))
      (node (ref "U2") (pin "3") (pinfunction "GND_3") (pintype "passive"))
      (node (ref "U2") (pin "6") (pinfunction "EPAD_6") (pintype "passive"))
      (node (ref "U3") (pin "22") (pinfunction "GND_2_22") (pintype "passive"))
      (node (ref "U3") (pin "8") (pinfunction "GND_1_8") (pintype "passive"))
      (node (ref "U4") (pin "3") (pinfunction "3_3") (pintype "passive"))
      (node (ref "U5") (pin "3") (pinfunction "3_3") (pintype "passive"))
      (node (ref "U6") (pin "3") (pinfunction "3_3") (pintype "passive"))
      (node (ref "U7") (pin "3") (pinfunction "3_3") (pintype "passive"))
      (node (ref "Z1") (pin "1") (pinfunction "1_1") (pintype "passive"))
      (node (ref "Z2") (pin "1") (pinfunction "1_1") (pintype "passive"))
    )
    (net (code "62") (name "Net-(C11-Pad1)") (class "Default")
      (node (ref "C11") (pin "1") (pinfunction "1_1") (pintype "passive"))
      (node (ref "JP3") (pin "1") (pinfunction "1_1") (pintype "passive"))
    )
    (net (code "63") (name "Net-(D1-Anode)") (class "Default")
      (node (ref "D1") (pin "2") (pinfunction "Anode_2") (pintype "passive"))
      (node (ref "R1") (pin "2") (pinfunction "2_2") (pintype "passive"))
    )
    (net (code "64") (name "Net-(D2-Anode)") (class "Default")
      (node (ref "D2") (pin "2") (pinfunction "Anode_2") (pintype "passive"))
      (node (ref "R2") (pin "1") (pinfunction "1_1") (pintype "passive"))
    )
    (net (code "65") (name "Net-(D3-Anode)") (class "Default")
      (node (ref "D3") (pin "2") (pinfunction "Anode_2") (pintype "passive"))
      (node (ref "R19") (pin "1") (pinfunction "1_1") (pintype "passive"))
    )
    (net (code "66") (name "Net-(D3-Cathode)") (class "Default")
      (node (ref "D3") (pin "1") (pinfunction "Cathode_1") (pintype "passive"))
      (node (ref "U4") (pin "4") (pinfunction "4_4") (pintype "passive"))
    )
    (net (code "67") (name "Net-(D4-Anode)") (class "Default")
      (node (ref "D4") (pin "2") (pinfunction "Anode_2") (pintype "passive"))
      (node (ref "R20") (pin "1") (pinfunction "1_1") (pintype "passive"))
    )
    (net (code "68") (name "Net-(D6-Anode)") (class "Default")
      (node (ref "D6") (pin "2") (pinfunction "Anode_2") (pintype "passive"))
      (node (ref "R24") (pin "1") (pinfunction "1_1") (pintype "passive"))
      (node (ref "R28") (pin "1") (pinfunction "1_1") (pintype "passive"))
    )
    (net (code "69") (name "Net-(J2-Pad4)") (class "Default")
      (node (ref "J2") (pin "4") (pinfunction "4_4") (pintype "passive"))
      (node (ref "R9") (pin "1") (pinfunction "1_1") (pintype "passive"))
    )
    (net (code "70") (name "Net-(JP3-Pad3)") (class "Default")
      (node (ref "JP3") (pin "3") (pinfunction "3_3") (pintype "passive"))
      (node (ref "R13") (pin "2") (pinfunction "2_2") (pintype "passive"))
    )
    (net (code "71") (name "Net-(R25-Pad1)") (class "Default")
      (node (ref "R25") (pin "1") (pinfunction "1_1") (pintype "passive"))
      (node (ref "U5") (pin "4") (pinfunction "4_4") (pintype "passive"))
    )
    (net (code "72") (name "unconnected-(J6-Pad1)") (class "Default")
      (node (ref "J6") (pin "1") (pinfunction "1_1") (pintype "passive+no_connect"))
    )
    (net (code "73") (name "unconnected-(J6-Pad8)") (class "Default")
      (node (ref "J6") (pin "8") (pinfunction "8_8") (pintype "passive+no_connect"))
    )
    (net (code "74") (name "unconnected-(MH1-Pad1)") (class "Default")
      (node (ref "MH1") (pin "1") (pinfunction "1_1") (pintype "passive+no_connect"))
    )
    (net (code "75") (name "unconnected-(U1-AIN0_{slash}_INT1_{slash}_PD1-Pad7)") (class "Default")
      (node (ref "U1") (pin "7") (pinfunction "AIN0_/_INT1_/_PD1_7") (pintype "passive+no_connect"))
    )
    (net (code "76") (name "unconnected-(U1-AIN2_{slash}_PCINT11_{slash}_PC2-Pad5)") (class "Default")
      (node (ref "U1") (pin "5") (pinfunction "AIN2_/_PCINT11_/_PC2_5") (pintype "passive+no_connect"))
    )
    (net (code "77") (name "unconnected-(U1-CLKO_{slash}_ICP1_{slash}_INT4_{slash}_PC7-Pad22)") (class "Default")
      (node (ref "U1") (pin "22") (pinfunction "CLKO_/_ICP1_/_INT4_/_PC7_22") (pintype "passive+no_connect"))
    )
    (net (code "78") (name "unconnected-(U1-OC.0B_{slash}_INT0{slash}_PD0-Pad6)") (class "Default")
      (node (ref "U1") (pin "6") (pinfunction "OC.0B_/_INT0/_PD0_6") (pintype "passive+no_connect"))
    )
    (net (code "79") (name "unconnected-(U1-OC.1A_{slash}_PCINT8_{slash}_PC6-Pad23)") (class "Default")
      (node (ref "U1") (pin "23") (pinfunction "OC.1A_/_PCINT8_/_PC6_23") (pintype "passive+no_connect"))
    )
    (net (code "80") (name "unconnected-(U1-OC.1B_{slash}_PCINT9_{slash}_PC5-Pad25)") (class "Default")
      (node (ref "U1") (pin "25") (pinfunction "OC.1B_/_PCINT9_/_PC5_25") (pintype "passive+no_connect"))
    )
    (net (code "81") (name "unconnected-(U1-PCINT10_{slash}_PC4-Pad26)") (class "Default")
      (node (ref "U1") (pin "26") (pinfunction "PCINT10_/_PC4_26") (pintype "passive+no_connect"))
    )
    (net (code "82") (name "unconnected-(U1-~{RTS}_{slash}_AIN5_{slash}_INT6_{slash}_PD6-Pad12)") (class "Default")
      (node (ref "U1") (pin "12") (pinfunction "~{RTS}_/_AIN5_/_INT6_/_PD6_12") (pintype "passive+no_connect"))
    )
    (net (code "83") (name "unconnected-(U1-~{SS}_{slash}_PCINT0_{slash}_PB0-Pad14)") (class "Default")
      (node (ref "U1") (pin "14") (pinfunction "~{SS}_/_PCINT0_/_PB0_14") (pintype "passive+no_connect"))
    )
  )
)
